# Gate_Driver_Connection.net
KiCad netlist of a schematic drawn in Altium Designer
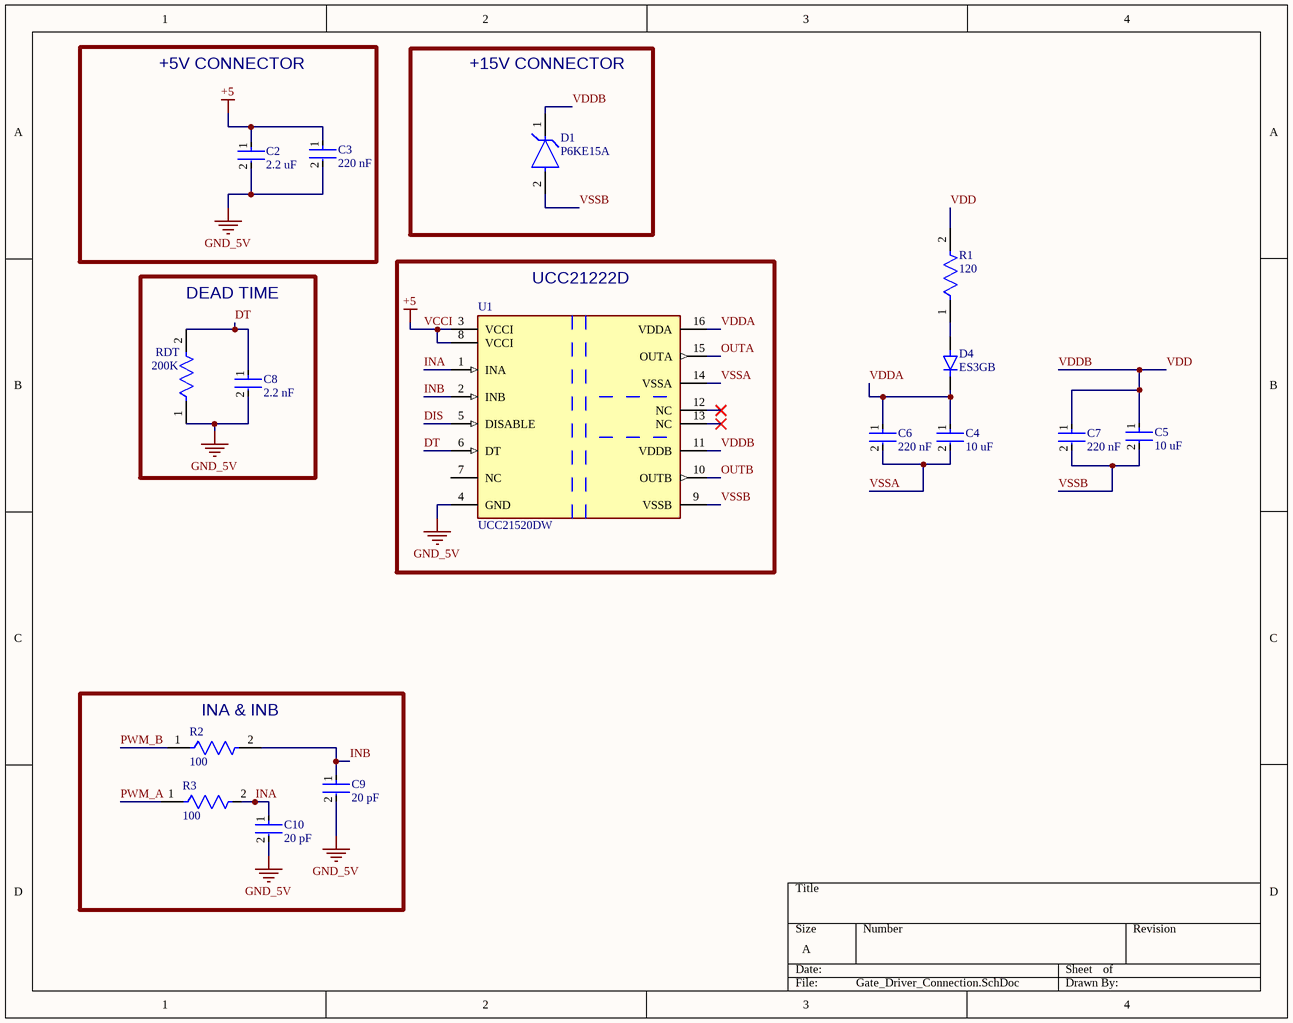
[diagram p0: Gate_Driver_Connection.SchDoc]

(export (version "E")
  (design (tool "Eeschema 10.0.6"))
  (components
    (comp (ref "C2")
      (value "2.2 uF")
      (footprint "FP-C0805C-DN-MFG")
      (description "CAP CER 0.22UF 50V X7R 0805")
      (fields
        (field (name "MANUFACTURER") "KEMET")
        (field (name "OCTOPART") "https://octopart.com/c0805c224k5ractu-kemet-144670")
      )
      (libsource (lib "Altium Content Vault") (part "b4654b650e69147ec39a6b967a45e02"))
    )
    (comp (ref "C3")
      (value "220 nF")
      (footprint "FP-C0805C-DN-MFG")
      (description "CAP CER 0.22UF 50V X7R 0805")
      (fields
        (field (name "MANUFACTURER") "KEMET")
        (field (name "OCTOPART") "https://octopart.com/c0805c224k5ractu-kemet-144670")
      )
      (libsource (lib "Altium Content Vault") (part "b4654b650e69147ec39a6b967a45e02"))
    )
    (comp (ref "C4")
      (value "10 uF")
      (footprint "FP-C0805C-DN-MFG")
      (description "CAP CER 0.22UF 50V X7R 0805")
      (fields
        (field (name "MANUFACTURER") "KEMET")
        (field (name "OCTOPART") "https://octopart.com/c0805c224k5ractu-kemet-144670")
      )
      (libsource (lib "Altium Content Vault") (part "b4654b650e69147ec39a6b967a45e02"))
    )
    (comp (ref "C5")
      (value "10 uF")
      (footprint "FP-C0805C-DN-MFG")
      (description "CAP CER 0.22UF 50V X7R 0805")
      (fields
        (field (name "MANUFACTURER") "KEMET")
        (field (name "OCTOPART") "https://octopart.com/c0805c224k5ractu-kemet-144670")
      )
      (libsource (lib "Altium Content Vault") (part "b4654b650e69147ec39a6b967a45e02"))
    )
    (comp (ref "C6")
      (value "220 nF")
      (footprint "FP-C0805C-DN-MFG")
      (description "CAP CER 0.22UF 50V X7R 0805")
      (fields
        (field (name "MANUFACTURER") "KEMET")
        (field (name "OCTOPART") "https://octopart.com/c0805c224k5ractu-kemet-144670")
      )
      (libsource (lib "Altium Content Vault") (part "b4654b650e69147ec39a6b967a45e02"))
    )
    (comp (ref "C7")
      (value "220 nF")
      (footprint "FP-C0805C-DN-MFG")
      (description "CAP CER 0.22UF 50V X7R 0805")
      (fields
        (field (name "MANUFACTURER") "KEMET")
        (field (name "OCTOPART") "https://octopart.com/c0805c224k5ractu-kemet-144670")
      )
      (libsource (lib "Altium Content Vault") (part "b4654b650e69147ec39a6b967a45e02"))
    )
    (comp (ref "C8")
      (value "2.2 nF")
      (footprint "FP-C0805C-DN-MFG")
      (description "CAP CER 0.22UF 50V X7R 0805")
      (fields
        (field (name "MANUFACTURER") "KEMET")
        (field (name "OCTOPART") "https://octopart.com/c0805c224k5ractu-kemet-144670")
      )
      (libsource (lib "Altium Content Vault") (part "b4654b650e69147ec39a6b967a45e02"))
    )
    (comp (ref "C9")
      (value "20 pF")
      (footprint "FP-C0805C-DN-MFG")
      (description "CAP CER 0.22UF 50V X7R 0805")
      (fields
        (field (name "MANUFACTURER") "KEMET")
        (field (name "OCTOPART") "https://octopart.com/c0805c224k5ractu-kemet-144670")
      )
      (libsource (lib "Altium Content Vault") (part "b4654b650e69147ec39a6b967a45e02"))
    )
    (comp (ref "C10")
      (value "20 pF")
      (footprint "FP-C0805C-DN-MFG")
      (description "CAP CER 0.22UF 50V X7R 0805")
      (fields
        (field (name "MANUFACTURER") "KEMET")
        (field (name "OCTOPART") "https://octopart.com/c0805c224k5ractu-kemet-144670")
      )
      (libsource (lib "Altium Content Vault") (part "b4654b650e69147ec39a6b967a45e02"))
    )
    (comp (ref "D1")
      (value "P6KE15A")
      (footprint "FP-DO-15-MFG")
      (description "P6KE15A 600 Watt SUR40 Transient Voltage Suppressor, 15 V, Unidirectional")
      (libsource (lib "Altium Content Vault") (part "f813f71cba58e380607f5dd3caf9714"))
    )
    (comp (ref "D4")
      (value "ES3GB")
      (footprint "ES3GB:DIOM4336X265N")
      (fields (field (name "MF") "{'manufacturer': u'Taiwan Semiconductor'}"))
      (libsource (lib "*") (part "ES3GB"))
    )
    (comp (ref "R1")
      (value "120")
      (footprint "FP-RC0805-0_6-IPC_C")
      (description "RES 100K OHM 1% 1/8W 0805")
      (fields (field (name "TOLERANCE") "1%"))
      (libsource (lib "Altium Content Vault") (part "1029c3af85768c4190bb7ad29bc67b5"))
    )
    (comp (ref "R2")
      (value "100")
      (footprint "FP-RC0805-0_6-IPC_C")
      (description "RES 100K OHM 1% 1/8W 0805")
      (fields (field (name "TOLERANCE") "1%"))
      (libsource (lib "Altium Content Vault") (part "1029c3af85768c4190bb7ad29bc67b5"))
    )
    (comp (ref "R3")
      (value "100")
      (footprint "FP-RC0805-0_6-IPC_C")
      (description "RES 100K OHM 1% 1/8W 0805")
      (fields (field (name "TOLERANCE") "1%"))
      (libsource (lib "Altium Content Vault") (part "1029c3af85768c4190bb7ad29bc67b5"))
    )
    (comp (ref "RDT")
      (value "200K")
      (footprint "FP-CF18-MFG")
      (description "RES 10K OHM 1/8W 5% CF AXIAL")
      (fields
        (field (name "MANUFACTURER PART NUMBER") "CF18JT10K0")
        (field (name "MANUFACTURER") "Stackpole Electronics")
      )
      (libsource (lib "Altium Content Vault") (part "1029c3af85768c4190bb7ad29bc67b5"))
    )
    (comp (ref "U1")
      (value "UCC21520DW")
      (footprint "FP-DW0016B-MFG")
      (description "DGTL ISO 5.7KV GATE DRVR 16SOIC")
      (libsource (lib "Altium Content Vault") (part "6a37a0897a27c2327358918c0ee180b"))
    )
  )
  (nets
    (net (code "1") (name "+5") (class "Default")
      (node (ref "C2") (pin "1") (pinfunction "1_1") (pintype "passive"))
      (node (ref "C3") (pin "1") (pinfunction "1_1") (pintype "passive"))
      (node (ref "U1") (pin "3") (pinfunction "VCCI_3") (pintype "power_in"))
      (node (ref "U1") (pin "8") (pinfunction "VCCI_8") (pintype "power_in"))
    )
    (net (code "2") (name "/DIS") (class "Default")
      (node (ref "U1") (pin "5") (pinfunction "DISABLE_5") (pintype "input"))
    )
    (net (code "3") (name "/DT") (class "Default")
      (node (ref "C8") (pin "1") (pinfunction "1_1") (pintype "passive"))
      (node (ref "RDT") (pin "2") (pinfunction "2_2") (pintype "passive"))
      (node (ref "U1") (pin "6") (pinfunction "DT_6") (pintype "input"))
    )
    (net (code "4") (name "/INA") (class "Default")
      (node (ref "C10") (pin "1") (pinfunction "1_1") (pintype "passive"))
      (node (ref "R3") (pin "2") (pinfunction "2_2") (pintype "passive"))
      (node (ref "U1") (pin "1") (pinfunction "INA_1") (pintype "input"))
    )
    (net (code "5") (name "/INB") (class "Default")
      (node (ref "C9") (pin "1") (pinfunction "1_1") (pintype "passive"))
      (node (ref "R2") (pin "2") (pinfunction "2_2") (pintype "passive"))
      (node (ref "U1") (pin "2") (pinfunction "INB_2") (pintype "input"))
    )
    (net (code "6") (name "/OUTA") (class "Default")
      (node (ref "U1") (pin "15") (pinfunction "OUTA_15") (pintype "output"))
    )
    (net (code "7") (name "/OUTB") (class "Default")
      (node (ref "U1") (pin "10") (pinfunction "OUTB_10") (pintype "output"))
    )
    (net (code "8") (name "/PWM_A") (class "Default")
      (node (ref "R3") (pin "1") (pinfunction "1_1") (pintype "passive"))
    )
    (net (code "9") (name "/PWM_B") (class "Default")
      (node (ref "R2") (pin "1") (pinfunction "1_1") (pintype "passive"))
    )
    (net (code "10") (name "/VDD") (class "Default")
      (node (ref "C5") (pin "1") (pinfunction "1_1") (pintype "passive"))
      (node (ref "C7") (pin "1") (pinfunction "1_1") (pintype "passive"))
      (node (ref "D1") (pin "1") (pinfunction "C_1") (pintype "passive"))
      (node (ref "R1") (pin "2") (pinfunction "2_2") (pintype "passive"))
      (node (ref "U1") (pin "11") (pinfunction "VDDB_11") (pintype "power_in"))
    )
    (net (code "11") (name "/VDDA") (class "Default")
      (node (ref "C4") (pin "1") (pinfunction "1_1") (pintype "passive"))
      (node (ref "C6") (pin "1") (pinfunction "1_1") (pintype "passive"))
      (node (ref "D4") (pin "C") (pinfunction "K_C") (pintype "passive"))
      (node (ref "U1") (pin "16") (pinfunction "VDDA_16") (pintype "power_in"))
    )
    (net (code "12") (name "/VSSA") (class "Default")
      (node (ref "C4") (pin "2") (pinfunction "2_2") (pintype "passive"))
      (node (ref "C6") (pin "2") (pinfunction "2_2") (pintype "passive"))
      (node (ref "U1") (pin "14") (pinfunction "VSSA_14") (pintype "power_in"))
    )
    (net (code "13") (name "/VSSB") (class "Default")
      (node (ref "C5") (pin "2") (pinfunction "2_2") (pintype "passive"))
      (node (ref "C7") (pin "2") (pinfunction "2_2") (pintype "passive"))
      (node (ref "D1") (pin "2") (pinfunction "A_2") (pintype "passive"))
      (node (ref "U1") (pin "9") (pinfunction "VSSB_9") (pintype "power_in"))
    )
    (net (code "14") (name "GND_5V") (class "Default")
      (node (ref "C10") (pin "2") (pinfunction "2_2") (pintype "passive"))
      (node (ref "C2") (pin "2") (pinfunction "2_2") (pintype "passive"))
      (node (ref "C3") (pin "2") (pinfunction "2_2") (pintype "passive"))
      (node (ref "C8") (pin "2") (pinfunction "2_2") (pintype "passive"))
      (node (ref "C9") (pin "2") (pinfunction "2_2") (pintype "passive"))
      (node (ref "RDT") (pin "1") (pinfunction "1_1") (pintype "passive"))
      (node (ref "U1") (pin "4") (pinfunction "GND_4") (pintype "power_in"))
    )
    (net (code "15") (name "Net-(D4-PadA)") (class "Default")
      (node (ref "D4") (pin "A") (pinfunction "A_A") (pintype "passive"))
      (node (ref "R1") (pin "1") (pinfunction "1_1") (pintype "passive"))
    )
    (net (code "16") (name "unconnected-(U1-NC-Pad7)") (class "Default")
      (node (ref "U1") (pin "7") (pinfunction "NC_7") (pintype "passive"))
    )
    (net (code "17") (name "unconnected-(U1-NC-Pad12)") (class "Default")
      (node (ref "U1") (pin "12") (pinfunction "NC_12") (pintype "passive+no_connect"))
    )
    (net (code "18") (name "unconnected-(U1-NC-Pad13)") (class "Default")
      (node (ref "U1") (pin "13") (pinfunction "NC_13") (pintype "passive+no_connect"))
    )
  )
)
